# gimbaldriver.net
KiCad netlist of a schematic drawn in EAGLE
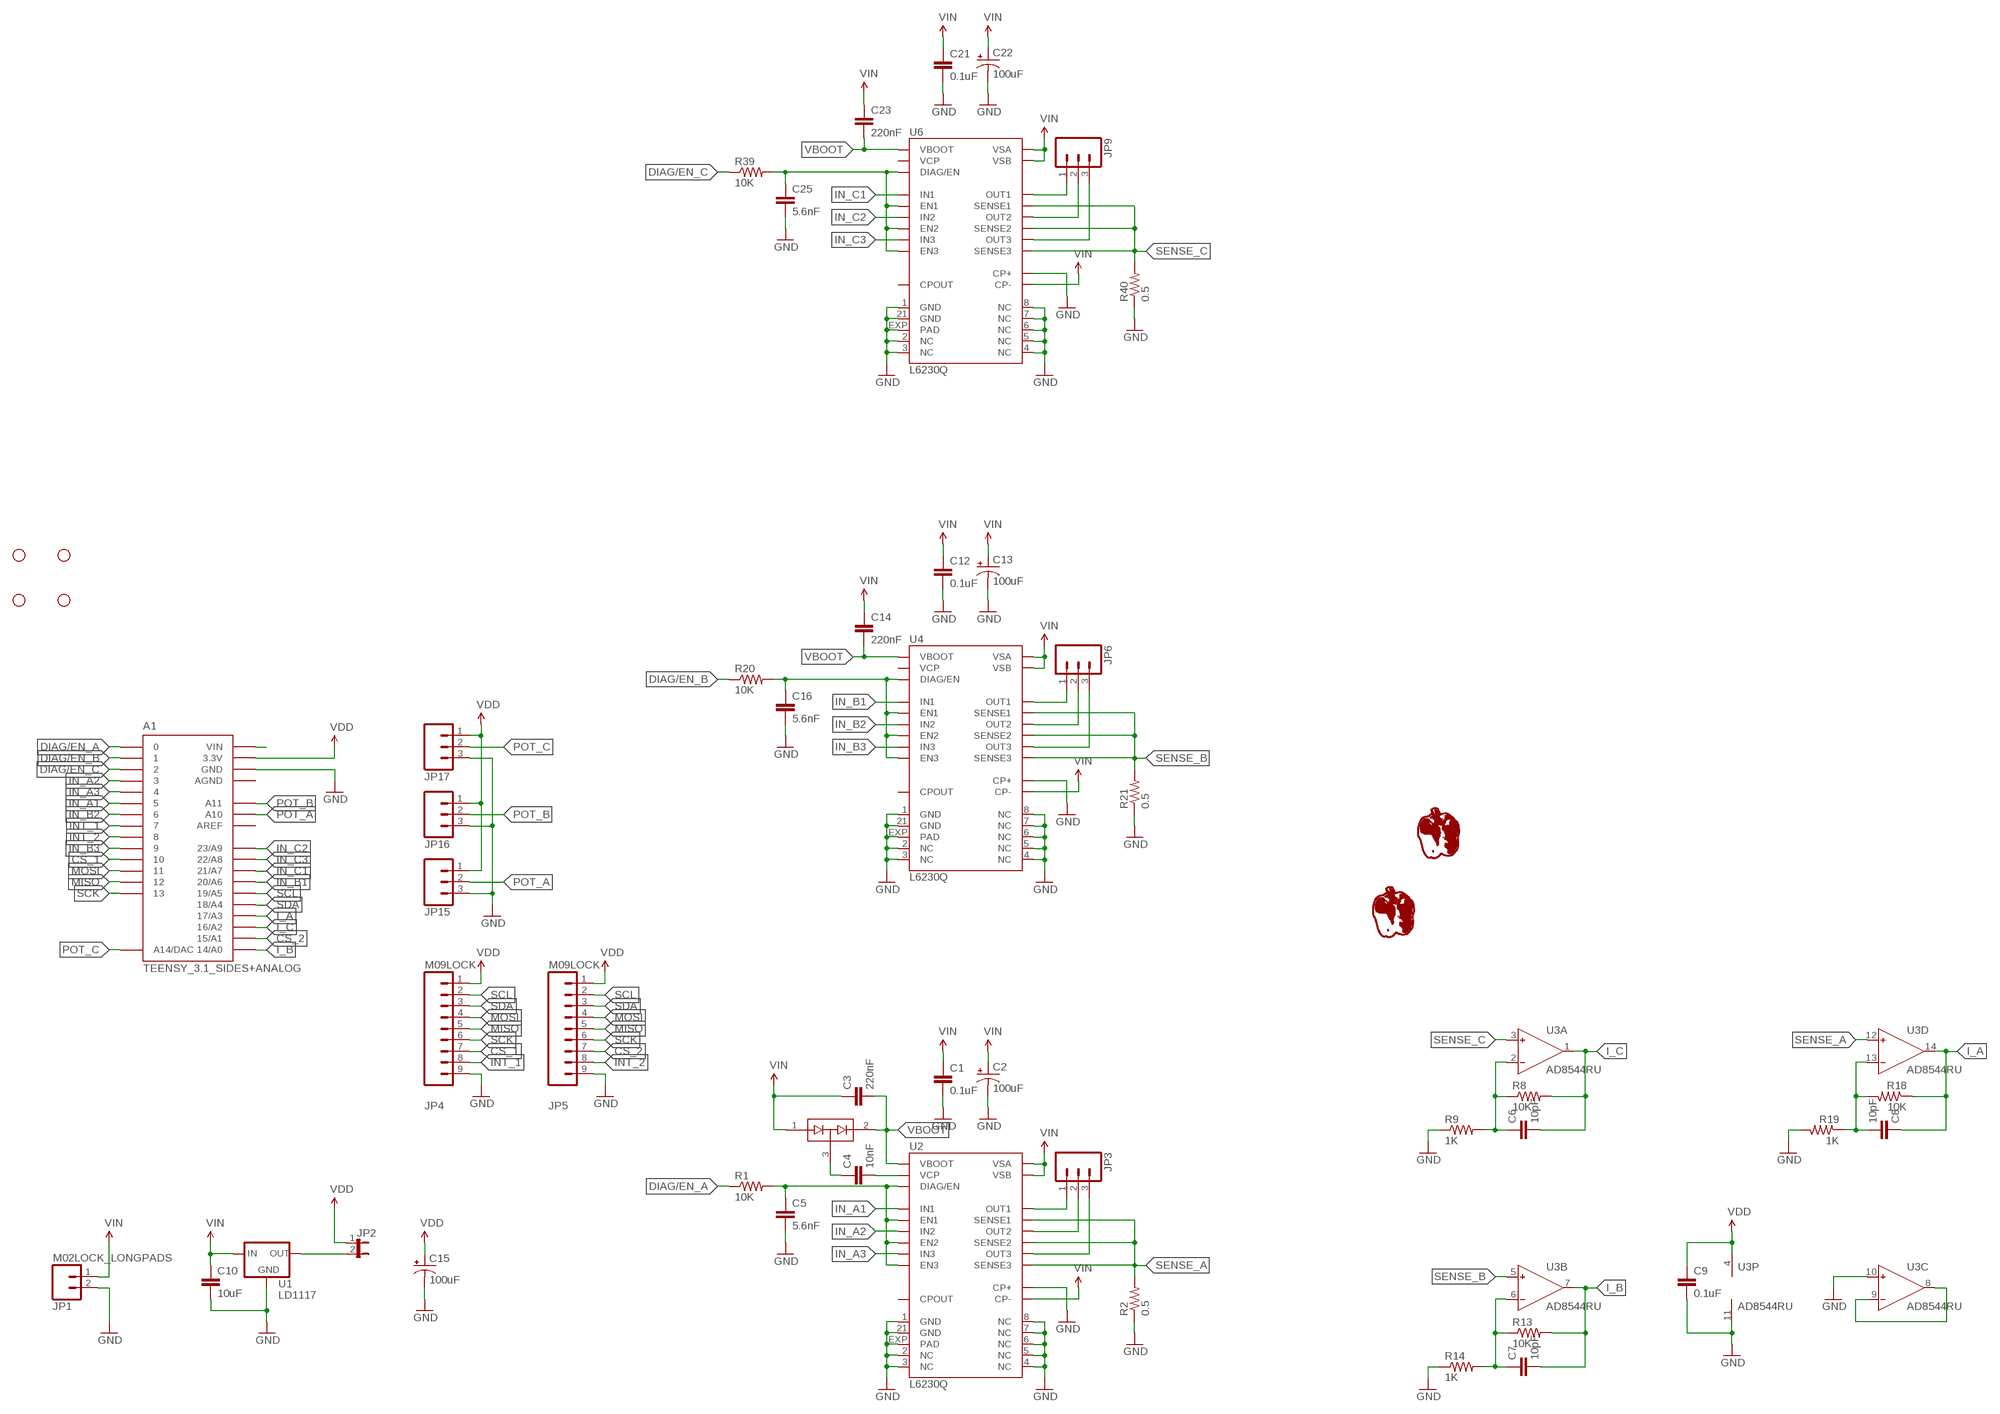
[diagram p0: schematic, sheet 1]

(export (version "E")
  (design (tool "Eeschema 10.0.6"))
  (components
    (comp (ref "A1")
      (value "TEENSY_3.1_SIDES+ANALOG")
      (footprint "eagle-import:TEENSY_3.1_SIDES+ANALOG")
      (libsource (lib "eagle-import") (part "TEENSY_3.1_SIDES+ANALOG"))
    )
    (comp (ref "C1")
      (value "0.1uF")
      (footprint "eagle-import:0603-CAP")
      (libsource (lib "eagle-import") (part "CAP0603-CAP"))
    )
    (comp (ref "C2")
      (value "100uF")
      (footprint "eagle-import:CPOL-RADIAL-100UF-25V")
      (libsource (lib "eagle-import") (part "CAP_POLPTH1"))
    )
    (comp (ref "C3")
      (value "220nF")
      (footprint "eagle-import:0603-CAP")
      (libsource (lib "eagle-import") (part "CAP0603-CAP"))
    )
    (comp (ref "C4")
      (value "10nF")
      (footprint "eagle-import:0603-CAP")
      (libsource (lib "eagle-import") (part "CAP0603-CAP"))
    )
    (comp (ref "C5")
      (value "5.6nF")
      (footprint "eagle-import:0603-CAP")
      (libsource (lib "eagle-import") (part "CAP0603-CAP"))
    )
    (comp (ref "C6")
      (value "10pF")
      (footprint "eagle-import:0603-CAP")
      (libsource (lib "eagle-import") (part "CAP0603-CAP"))
    )
    (comp (ref "C7")
      (value "10pF")
      (footprint "eagle-import:0603-CAP")
      (libsource (lib "eagle-import") (part "CAP0603-CAP"))
    )
    (comp (ref "C8")
      (value "10pF")
      (footprint "eagle-import:0603-CAP")
      (libsource (lib "eagle-import") (part "CAP0603-CAP"))
    )
    (comp (ref "C9")
      (value "0.1uF")
      (footprint "eagle-import:0603-CAP")
      (libsource (lib "eagle-import") (part "CAP0603-CAP"))
    )
    (comp (ref "C10")
      (value "10uF")
      (footprint "eagle-import:1206")
      (libsource (lib "eagle-import") (part "CAP1206"))
    )
    (comp (ref "C12")
      (value "0.1uF")
      (footprint "eagle-import:0603-CAP")
      (libsource (lib "eagle-import") (part "CAP0603-CAP"))
    )
    (comp (ref "C13")
      (value "100uF")
      (footprint "eagle-import:CPOL-RADIAL-100UF-25V")
      (libsource (lib "eagle-import") (part "CAP_POLPTH1"))
    )
    (comp (ref "C14")
      (value "220nF")
      (footprint "eagle-import:0603-CAP")
      (libsource (lib "eagle-import") (part "CAP0603-CAP"))
    )
    (comp (ref "C15")
      (value "100uF")
      (footprint "eagle-import:CPOL-RADIAL-100UF-25V")
      (libsource (lib "eagle-import") (part "CAP_POLPTH1"))
    )
    (comp (ref "C16")
      (value "5.6nF")
      (footprint "eagle-import:0603-CAP")
      (libsource (lib "eagle-import") (part "CAP0603-CAP"))
    )
    (comp (ref "C21")
      (value "0.1uF")
      (footprint "eagle-import:0603-CAP")
      (libsource (lib "eagle-import") (part "CAP0603-CAP"))
    )
    (comp (ref "C22")
      (value "100uF")
      (footprint "eagle-import:CPOL-RADIAL-100UF-25V")
      (libsource (lib "eagle-import") (part "CAP_POLPTH1"))
    )
    (comp (ref "C23")
      (value "220nF")
      (footprint "eagle-import:0603-CAP")
      (libsource (lib "eagle-import") (part "CAP0603-CAP"))
    )
    (comp (ref "C25")
      (value "5.6nF")
      (footprint "eagle-import:0603-CAP")
      (libsource (lib "eagle-import") (part "CAP0603-CAP"))
    )
    (comp (ref "D1")
      (value "BAV99")
      (footprint "eagle-import:SOT23")
      (libsource (lib "eagle-import") (part "BAV99"))
    )
    (comp (ref "JP1")
      (value "M02LOCK_LONGPADS")
      (footprint "eagle-import:1X02_LOCK_LONGPADS")
      (libsource (lib "eagle-import") (part "M02LOCK_LONGPADS"))
    )
    (comp (ref "JP2")
      (value "JUMPER-2PTH_LOCK")
      (footprint "eagle-import:1X02_LOCK")
      (libsource (lib "eagle-import") (part "JUMPER-2PTH_LOCK"))
    )
    (comp (ref "JP3")
      (value "M03LOCK_LONGPADS")
      (footprint "eagle-import:1X03_LOCK_LONGPADS")
      (libsource (lib "eagle-import") (part "M03LOCK_LONGPADS"))
    )
    (comp (ref "JP4")
      (value "M09LOCK")
      (footprint "eagle-import:1X09_LOCK")
      (libsource (lib "eagle-import") (part "M09LOCK"))
    )
    (comp (ref "JP5")
      (value "M09LOCK")
      (footprint "eagle-import:1X09_LOCK")
      (libsource (lib "eagle-import") (part "M09LOCK"))
    )
    (comp (ref "JP6")
      (value "M03LOCK_LONGPADS")
      (footprint "eagle-import:1X03_LOCK_LONGPADS")
      (libsource (lib "eagle-import") (part "M03LOCK_LONGPADS"))
    )
    (comp (ref "JP9")
      (value "M03LOCK_LONGPADS")
      (footprint "eagle-import:1X03_LOCK_LONGPADS")
      (libsource (lib "eagle-import") (part "M03LOCK_LONGPADS"))
    )
    (comp (ref "JP15")
      (value "M03LOCK")
      (footprint "eagle-import:1X03_LOCK")
      (libsource (lib "eagle-import") (part "M03LOCK"))
    )
    (comp (ref "JP16")
      (value "M03LOCK")
      (footprint "eagle-import:1X03_LOCK")
      (libsource (lib "eagle-import") (part "M03LOCK"))
    )
    (comp (ref "JP17")
      (value "M03LOCK")
      (footprint "eagle-import:1X03_LOCK")
      (libsource (lib "eagle-import") (part "M03LOCK"))
    )
    (comp (ref "R1")
      (value "10K")
      (footprint "eagle-import:0603-RES")
      (libsource (lib "eagle-import") (part "RESISTOR0603-RES"))
    )
    (comp (ref "R2")
      (value "0.5")
      (footprint "eagle-import:1206")
      (libsource (lib "eagle-import") (part "RESISTOR1206"))
    )
    (comp (ref "R8")
      (value "10K")
      (footprint "eagle-import:0603-RES")
      (libsource (lib "eagle-import") (part "RESISTOR0603-RES"))
    )
    (comp (ref "R9")
      (value "1K")
      (footprint "eagle-import:0603-RES")
      (libsource (lib "eagle-import") (part "RESISTOR0603-RES"))
    )
    (comp (ref "R13")
      (value "10K")
      (footprint "eagle-import:0603-RES")
      (libsource (lib "eagle-import") (part "RESISTOR0603-RES"))
    )
    (comp (ref "R14")
      (value "1K")
      (footprint "eagle-import:0603-RES")
      (libsource (lib "eagle-import") (part "RESISTOR0603-RES"))
    )
    (comp (ref "R18")
      (value "10K")
      (footprint "eagle-import:0603-RES")
      (libsource (lib "eagle-import") (part "RESISTOR0603-RES"))
    )
    (comp (ref "R19")
      (value "1K")
      (footprint "eagle-import:0603-RES")
      (libsource (lib "eagle-import") (part "RESISTOR0603-RES"))
    )
    (comp (ref "R20")
      (value "10K")
      (footprint "eagle-import:0603-RES")
      (libsource (lib "eagle-import") (part "RESISTOR0603-RES"))
    )
    (comp (ref "R21")
      (value "0.5")
      (footprint "eagle-import:1206")
      (libsource (lib "eagle-import") (part "RESISTOR1206"))
    )
    (comp (ref "R39")
      (value "10K")
      (footprint "eagle-import:0603-RES")
      (libsource (lib "eagle-import") (part "RESISTOR0603-RES"))
    )
    (comp (ref "R40")
      (value "0.5")
      (footprint "eagle-import:1206")
      (libsource (lib "eagle-import") (part "RESISTOR1206"))
    )
    (comp (ref "STANDOFF1")
      (value "STAND-OFF")
      (footprint "eagle-import:STAND-OFF")
      (libsource (lib "eagle-import") (part "STAND-OFF"))
    )
    (comp (ref "STANDOFF2")
      (value "STAND-OFF")
      (footprint "eagle-import:STAND-OFF")
      (libsource (lib "eagle-import") (part "STAND-OFF"))
    )
    (comp (ref "STANDOFF3")
      (value "STAND-OFF")
      (footprint "eagle-import:STAND-OFF")
      (libsource (lib "eagle-import") (part "STAND-OFF"))
    )
    (comp (ref "STANDOFF4")
      (value "STAND-OFF")
      (footprint "eagle-import:STAND-OFF")
      (libsource (lib "eagle-import") (part "STAND-OFF"))
    )
    (comp (ref "U$1")
      (value "GIMP-PEPPER")
      (footprint "eagle-import:GIMP-PEPPER")
      (libsource (lib "eagle-import") (part "GIMP-PEPPER"))
    )
    (comp (ref "U$2")
      (value "GIMBALV1")
      (footprint "eagle-import:GIMBALV1")
      (libsource (lib "eagle-import") (part "GIMBALV1"))
    )
    (comp (ref "U1")
      (value "LD1117")
      (footprint "eagle-import:SOT-223")
      (libsource (lib "eagle-import") (part "LD1117"))
    )
    (comp (ref "U2")
      (value "L6230Q")
      (footprint "eagle-import:VFQFPN-32")
      (libsource (lib "eagle-import") (part "L6230Q"))
    )
    (comp (ref "U3")
      (value "AD8544RU")
      (footprint "eagle-import:TSSOP14")
      (fields (field (name "MPN") "AD8544ARUZ"))
      (libsource (lib "eagle-import") (part "AD8544RU"))
    )
    (comp (ref "U4")
      (value "L6230Q")
      (footprint "eagle-import:VFQFPN-32")
      (libsource (lib "eagle-import") (part "L6230Q"))
    )
    (comp (ref "U6")
      (value "L6230Q")
      (footprint "eagle-import:VFQFPN-32")
      (libsource (lib "eagle-import") (part "L6230Q"))
    )
  )
  (nets
    (net (code "1") (name "/AGND") (class "Default")
      (node (ref "A1") (pin "AGND") (pinfunction "AGND_AGND") (pintype "power_in"))
    )
    (net (code "2") (name "CS_1") (class "Default")
      (node (ref "A1") (pin "10") (pinfunction "10_10") (pintype "bidirectional"))
      (node (ref "JP4") (pin "7") (pinfunction "7_7") (pintype "passive"))
    )
    (net (code "3") (name "CS_2") (class "Default")
      (node (ref "A1") (pin "15/A1") (pinfunction "15/A1_15/A1") (pintype "bidirectional"))
      (node (ref "JP5") (pin "7") (pinfunction "7_7") (pintype "passive"))
    )
    (net (code "4") (name "DIAG{slash}EN_A") (class "Default")
      (node (ref "A1") (pin "0") (pinfunction "0_0") (pintype "bidirectional"))
      (node (ref "R1") (pin "1") (pinfunction "1_1") (pintype "passive"))
    )
    (net (code "5") (name "DIAG{slash}EN_B") (class "Default")
      (node (ref "A1") (pin "1") (pinfunction "1_1") (pintype "bidirectional"))
      (node (ref "R20") (pin "1") (pinfunction "1_1") (pintype "passive"))
    )
    (net (code "6") (name "DIAG{slash}EN_C") (class "Default")
      (node (ref "A1") (pin "2") (pinfunction "2_2") (pintype "bidirectional"))
      (node (ref "R39") (pin "1") (pinfunction "1_1") (pintype "passive"))
    )
    (net (code "7") (name "GND") (class "Default")
      (node (ref "A1") (pin "GND") (pinfunction "GND_GND") (pintype "power_in"))
      (node (ref "C1") (pin "2") (pinfunction "2_2") (pintype "passive"))
      (node (ref "C10") (pin "2") (pinfunction "2_2") (pintype "passive"))
      (node (ref "C12") (pin "2") (pinfunction "2_2") (pintype "passive"))
      (node (ref "C13") (pin "2") (pinfunction "-_2") (pintype "passive"))
      (node (ref "C15") (pin "2") (pinfunction "-_2") (pintype "passive"))
      (node (ref "C16") (pin "2") (pinfunction "2_2") (pintype "passive"))
      (node (ref "C2") (pin "2") (pinfunction "-_2") (pintype "passive"))
      (node (ref "C21") (pin "2") (pinfunction "2_2") (pintype "passive"))
      (node (ref "C22") (pin "2") (pinfunction "-_2") (pintype "passive"))
      (node (ref "C25") (pin "2") (pinfunction "2_2") (pintype "passive"))
      (node (ref "C5") (pin "2") (pinfunction "2_2") (pintype "passive"))
      (node (ref "C9") (pin "2") (pinfunction "2_2") (pintype "passive"))
      (node (ref "JP1") (pin "2") (pinfunction "2_2") (pintype "passive"))
      (node (ref "JP15") (pin "3") (pinfunction "3_3") (pintype "passive"))
      (node (ref "JP16") (pin "3") (pinfunction "3_3") (pintype "passive"))
      (node (ref "JP17") (pin "3") (pinfunction "3_3") (pintype "passive"))
      (node (ref "JP4") (pin "9") (pinfunction "9_9") (pintype "passive"))
      (node (ref "JP5") (pin "9") (pinfunction "9_9") (pintype "passive"))
      (node (ref "R14") (pin "1") (pinfunction "1_1") (pintype "passive"))
      (node (ref "R19") (pin "2") (pinfunction "2_2") (pintype "passive"))
      (node (ref "R2") (pin "1") (pinfunction "1_1") (pintype "passive"))
      (node (ref "R21") (pin "1") (pinfunction "1_1") (pintype "passive"))
      (node (ref "R40") (pin "1") (pinfunction "1_1") (pintype "passive"))
      (node (ref "R9") (pin "1") (pinfunction "1_1") (pintype "passive"))
      (node (ref "U1") (pin "1") (pinfunction "GND_1") (pintype "input"))
      (node (ref "U2") (pin "1") (pinfunction "GND_1") (pintype "bidirectional"))
      (node (ref "U2") (pin "2") (pinfunction "NC_2") (pintype "bidirectional"))
      (node (ref "U2") (pin "21") (pinfunction "GND_21") (pintype "bidirectional"))
      (node (ref "U2") (pin "3") (pinfunction "NC_3") (pintype "bidirectional"))
      (node (ref "U2") (pin "30") (pinfunction "CP+_30") (pintype "bidirectional"))
      (node (ref "U2") (pin "4") (pinfunction "NC_4") (pintype "bidirectional"))
      (node (ref "U2") (pin "5") (pinfunction "NC_5") (pintype "bidirectional"))
      (node (ref "U2") (pin "6") (pinfunction "NC_6") (pintype "bidirectional"))
      (node (ref "U2") (pin "7") (pinfunction "NC_7") (pintype "bidirectional"))
      (node (ref "U2") (pin "8") (pinfunction "NC_8") (pintype "bidirectional"))
      (node (ref "U2") (pin "EXP") (pinfunction "PAD_EXP") (pintype "bidirectional"))
      (node (ref "U3") (pin "10") (pinfunction "IN+_10") (pintype "input"))
      (node (ref "U3") (pin "11") (pinfunction "V-_11") (pintype "power_in"))
      (node (ref "U4") (pin "1") (pinfunction "GND_1") (pintype "bidirectional"))
      (node (ref "U4") (pin "2") (pinfunction "NC_2") (pintype "bidirectional"))
      (node (ref "U4") (pin "21") (pinfunction "GND_21") (pintype "bidirectional"))
      (node (ref "U4") (pin "3") (pinfunction "NC_3") (pintype "bidirectional"))
      (node (ref "U4") (pin "30") (pinfunction "CP+_30") (pintype "bidirectional"))
      (node (ref "U4") (pin "4") (pinfunction "NC_4") (pintype "bidirectional"))
      (node (ref "U4") (pin "5") (pinfunction "NC_5") (pintype "bidirectional"))
      (node (ref "U4") (pin "6") (pinfunction "NC_6") (pintype "bidirectional"))
      (node (ref "U4") (pin "7") (pinfunction "NC_7") (pintype "bidirectional"))
      (node (ref "U4") (pin "8") (pinfunction "NC_8") (pintype "bidirectional"))
      (node (ref "U4") (pin "EXP") (pinfunction "PAD_EXP") (pintype "bidirectional"))
      (node (ref "U6") (pin "1") (pinfunction "GND_1") (pintype "bidirectional"))
      (node (ref "U6") (pin "2") (pinfunction "NC_2") (pintype "bidirectional"))
      (node (ref "U6") (pin "21") (pinfunction "GND_21") (pintype "bidirectional"))
      (node (ref "U6") (pin "3") (pinfunction "NC_3") (pintype "bidirectional"))
      (node (ref "U6") (pin "30") (pinfunction "CP+_30") (pintype "bidirectional"))
      (node (ref "U6") (pin "4") (pinfunction "NC_4") (pintype "bidirectional"))
      (node (ref "U6") (pin "5") (pinfunction "NC_5") (pintype "bidirectional"))
      (node (ref "U6") (pin "6") (pinfunction "NC_6") (pintype "bidirectional"))
      (node (ref "U6") (pin "7") (pinfunction "NC_7") (pintype "bidirectional"))
      (node (ref "U6") (pin "8") (pinfunction "NC_8") (pintype "bidirectional"))
      (node (ref "U6") (pin "EXP") (pinfunction "PAD_EXP") (pintype "bidirectional"))
    )
    (net (code "8") (name "INT_1") (class "Default")
      (node (ref "A1") (pin "7") (pinfunction "7_7") (pintype "bidirectional"))
      (node (ref "JP4") (pin "8") (pinfunction "8_8") (pintype "passive"))
    )
    (net (code "9") (name "INT_2") (class "Default")
      (node (ref "A1") (pin "8") (pinfunction "8_8") (pintype "bidirectional"))
      (node (ref "JP5") (pin "8") (pinfunction "8_8") (pintype "passive"))
    )
    (net (code "10") (name "IN_A1") (class "Default")
      (node (ref "A1") (pin "5") (pinfunction "5_5") (pintype "bidirectional"))
      (node (ref "U2") (pin "26") (pinfunction "IN1_26") (pintype "bidirectional"))
    )
    (net (code "11") (name "IN_A2") (class "Default")
      (node (ref "A1") (pin "3") (pinfunction "3_3") (pintype "bidirectional"))
      (node (ref "U2") (pin "13") (pinfunction "IN2_13") (pintype "bidirectional"))
    )
    (net (code "12") (name "IN_A3") (class "Default")
      (node (ref "A1") (pin "4") (pinfunction "4_4") (pintype "bidirectional"))
      (node (ref "U2") (pin "28") (pinfunction "IN3_28") (pintype "bidirectional"))
    )
    (net (code "13") (name "IN_B1") (class "Default")
      (node (ref "A1") (pin "20/A6") (pinfunction "20/A6_20/A6") (pintype "bidirectional"))
      (node (ref "U4") (pin "26") (pinfunction "IN1_26") (pintype "bidirectional"))
    )
    (net (code "14") (name "IN_B2") (class "Default")
      (node (ref "A1") (pin "6") (pinfunction "6_6") (pintype "bidirectional"))
      (node (ref "U4") (pin "13") (pinfunction "IN2_13") (pintype "bidirectional"))
    )
    (net (code "15") (name "IN_B3") (class "Default")
      (node (ref "A1") (pin "9") (pinfunction "9_9") (pintype "bidirectional"))
      (node (ref "U4") (pin "28") (pinfunction "IN3_28") (pintype "bidirectional"))
    )
    (net (code "16") (name "IN_C1") (class "Default")
      (node (ref "A1") (pin "21/A7") (pinfunction "21/A7_21/A7") (pintype "bidirectional"))
      (node (ref "U6") (pin "26") (pinfunction "IN1_26") (pintype "bidirectional"))
    )
    (net (code "17") (name "IN_C2") (class "Default")
      (node (ref "A1") (pin "23/A9") (pinfunction "23/A9_23/A9") (pintype "bidirectional"))
      (node (ref "U6") (pin "13") (pinfunction "IN2_13") (pintype "bidirectional"))
    )
    (net (code "18") (name "IN_C3") (class "Default")
      (node (ref "A1") (pin "22/A8") (pinfunction "22/A8_22/A8") (pintype "bidirectional"))
      (node (ref "U6") (pin "28") (pinfunction "IN3_28") (pintype "bidirectional"))
    )
    (net (code "19") (name "I_A") (class "Default")
      (node (ref "A1") (pin "17/A3") (pinfunction "17/A3_17/A3") (pintype "bidirectional"))
      (node (ref "C8") (pin "1") (pinfunction "1_1") (pintype "passive"))
      (node (ref "R18") (pin "1") (pinfunction "1_1") (pintype "passive"))
      (node (ref "U3") (pin "14") (pinfunction "OUT_14") (pintype "output"))
    )
    (net (code "20") (name "I_B") (class "Default")
      (node (ref "A1") (pin "14/A0") (pinfunction "14/A0_14/A0") (pintype "bidirectional"))
      (node (ref "C7") (pin "2") (pinfunction "2_2") (pintype "passive"))
      (node (ref "R13") (pin "2") (pinfunction "2_2") (pintype "passive"))
      (node (ref "U3") (pin "7") (pinfunction "OUT_7") (pintype "output"))
    )
    (net (code "21") (name "I_C") (class "Default")
      (node (ref "A1") (pin "16/A2") (pinfunction "16/A2_16/A2") (pintype "bidirectional"))
      (node (ref "C6") (pin "2") (pinfunction "2_2") (pintype "passive"))
      (node (ref "R8") (pin "2") (pinfunction "2_2") (pintype "passive"))
      (node (ref "U3") (pin "1") (pinfunction "OUT_1") (pintype "output"))
    )
    (net (code "22") (name "MISO") (class "Default")
      (node (ref "A1") (pin "12") (pinfunction "12_12") (pintype "bidirectional"))
      (node (ref "JP4") (pin "5") (pinfunction "5_5") (pintype "passive"))
      (node (ref "JP5") (pin "5") (pinfunction "5_5") (pintype "passive"))
    )
    (net (code "23") (name "MOSI") (class "Default")
      (node (ref "A1") (pin "11") (pinfunction "11_11") (pintype "bidirectional"))
      (node (ref "JP4") (pin "4") (pinfunction "4_4") (pintype "passive"))
      (node (ref "JP5") (pin "4") (pinfunction "4_4") (pintype "passive"))
    )
    (net (code "24") (name "Net-(D1-COM)") (class "Default")
      (node (ref "C4") (pin "1") (pinfunction "1_1") (pintype "passive"))
      (node (ref "D1") (pin "3") (pinfunction "COM_3") (pintype "bidirectional"))
    )
    (net (code "25") (name "Net-(JP2-Pad2)") (class "Default")
      (node (ref "JP2") (pin "2") (pinfunction "2_2") (pintype "passive"))
      (node (ref "U1") (pin "2") (pinfunction "OUT_2") (pintype "passive"))
      (node (ref "U1") (pin "4") (pinfunction "OUT_4") (pintype "passive"))
    )
    (net (code "26") (name "Net-(U2-DIAG{slash}EN)") (class "Default")
      (node (ref "C5") (pin "1") (pinfunction "1_1") (pintype "passive"))
      (node (ref "R1") (pin "2") (pinfunction "2_2") (pintype "passive"))
      (node (ref "U2") (pin "14") (pinfunction "EN2_14") (pintype "bidirectional"))
      (node (ref "U2") (pin "16") (pinfunction "EN3_16") (pintype "bidirectional"))
      (node (ref "U2") (pin "27") (pinfunction "EN1_27") (pintype "bidirectional"))
      (node (ref "U2") (pin "9") (pinfunction "DIAG/EN_9") (pintype "bidirectional"))
    )
    (net (code "27") (name "Net-(U2-OUT1)") (class "Default")
      (node (ref "JP3") (pin "1") (pinfunction "1_1") (pintype "passive"))
      (node (ref "U2") (pin "31") (pinfunction "OUT1_31") (pintype "bidirectional"))
    )
    (net (code "28") (name "Net-(U2-OUT2)") (class "Default")
      (node (ref "JP3") (pin "2") (pinfunction "2_2") (pintype "passive"))
      (node (ref "U2") (pin "23") (pinfunction "OUT2_23") (pintype "bidirectional"))
    )
    (net (code "29") (name "Net-(U2-OUT3)") (class "Default")
      (node (ref "JP3") (pin "3") (pinfunction "3_3") (pintype "passive"))
      (node (ref "U2") (pin "19") (pinfunction "OUT3_19") (pintype "bidirectional"))
    )
    (net (code "30") (name "Net-(U2-VCP)") (class "Default")
      (node (ref "C4") (pin "2") (pinfunction "2_2") (pintype "passive"))
      (node (ref "U2") (pin "24") (pinfunction "VCP_24") (pintype "bidirectional"))
    )
    (net (code "31") (name "Net-(U3A-IN-)") (class "Default")
      (node (ref "C6") (pin "1") (pinfunction "1_1") (pintype "passive"))
      (node (ref "R8") (pin "1") (pinfunction "1_1") (pintype "passive"))
      (node (ref "R9") (pin "2") (pinfunction "2_2") (pintype "passive"))
      (node (ref "U3") (pin "2") (pinfunction "IN-_2") (pintype "input"))
    )
    (net (code "32") (name "Net-(U3B-IN-)") (class "Default")
      (node (ref "C7") (pin "1") (pinfunction "1_1") (pintype "passive"))
      (node (ref "R13") (pin "1") (pinfunction "1_1") (pintype "passive"))
      (node (ref "R14") (pin "2") (pinfunction "2_2") (pintype "passive"))
      (node (ref "U3") (pin "6") (pinfunction "IN-_6") (pintype "input"))
    )
    (net (code "33") (name "Net-(U3C-IN-)") (class "Default")
      (node (ref "U3") (pin "8") (pinfunction "OUT_8") (pintype "output"))
      (node (ref "U3") (pin "9") (pinfunction "IN-_9") (pintype "input"))
    )
    (net (code "34") (name "Net-(U3D-IN-)") (class "Default")
      (node (ref "C8") (pin "2") (pinfunction "2_2") (pintype "passive"))
      (node (ref "R18") (pin "2") (pinfunction "2_2") (pintype "passive"))
      (node (ref "R19") (pin "1") (pinfunction "1_1") (pintype "passive"))
      (node (ref "U3") (pin "13") (pinfunction "IN-_13") (pintype "input"))
    )
    (net (code "35") (name "Net-(U4-DIAG{slash}EN)") (class "Default")
      (node (ref "C16") (pin "1") (pinfunction "1_1") (pintype "passive"))
      (node (ref "R20") (pin "2") (pinfunction "2_2") (pintype "passive"))
      (node (ref "U4") (pin "14") (pinfunction "EN2_14") (pintype "bidirectional"))
      (node (ref "U4") (pin "16") (pinfunction "EN3_16") (pintype "bidirectional"))
      (node (ref "U4") (pin "27") (pinfunction "EN1_27") (pintype "bidirectional"))
      (node (ref "U4") (pin "9") (pinfunction "DIAG/EN_9") (pintype "bidirectional"))
    )
    (net (code "36") (name "Net-(U4-OUT1)") (class "Default")
      (node (ref "JP6") (pin "1") (pinfunction "1_1") (pintype "passive"))
      (node (ref "U4") (pin "31") (pinfunction "OUT1_31") (pintype "bidirectional"))
    )
    (net (code "37") (name "Net-(U4-OUT2)") (class "Default")
      (node (ref "JP6") (pin "2") (pinfunction "2_2") (pintype "passive"))
      (node (ref "U4") (pin "23") (pinfunction "OUT2_23") (pintype "bidirectional"))
    )
    (net (code "38") (name "Net-(U4-OUT3)") (class "Default")
      (node (ref "JP6") (pin "3") (pinfunction "3_3") (pintype "passive"))
      (node (ref "U4") (pin "19") (pinfunction "OUT3_19") (pintype "bidirectional"))
    )
    (net (code "39") (name "Net-(U6-DIAG{slash}EN)") (class "Default")
      (node (ref "C25") (pin "1") (pinfunction "1_1") (pintype "passive"))
      (node (ref "R39") (pin "2") (pinfunction "2_2") (pintype "passive"))
      (node (ref "U6") (pin "14") (pinfunction "EN2_14") (pintype "bidirectional"))
      (node (ref "U6") (pin "16") (pinfunction "EN3_16") (pintype "bidirectional"))
      (node (ref "U6") (pin "27") (pinfunction "EN1_27") (pintype "bidirectional"))
      (node (ref "U6") (pin "9") (pinfunction "DIAG/EN_9") (pintype "bidirectional"))
    )
    (net (code "40") (name "Net-(U6-OUT1)") (class "Default")
      (node (ref "JP9") (pin "1") (pinfunction "1_1") (pintype "passive"))
      (node (ref "U6") (pin "31") (pinfunction "OUT1_31") (pintype "bidirectional"))
    )
    (net (code "41") (name "Net-(U6-OUT2)") (class "Default")
      (node (ref "JP9") (pin "2") (pinfunction "2_2") (pintype "passive"))
      (node (ref "U6") (pin "23") (pinfunction "OUT2_23") (pintype "bidirectional"))
    )
    (net (code "42") (name "Net-(U6-OUT3)") (class "Default")
      (node (ref "JP9") (pin "3") (pinfunction "3_3") (pintype "passive"))
      (node (ref "U6") (pin "19") (pinfunction "OUT3_19") (pintype "bidirectional"))
    )
    (net (code "43") (name "POT_A") (class "Default")
      (node (ref "A1") (pin "A10") (pinfunction "A10_A10") (pintype "bidirectional"))
      (node (ref "JP15") (pin "2") (pinfunction "2_2") (pintype "passive"))
    )
    (net (code "44") (name "POT_B") (class "Default")
      (node (ref "A1") (pin "A11") (pinfunction "A11_A11") (pintype "bidirectional"))
      (node (ref "JP16") (pin "2") (pinfunction "2_2") (pintype "passive"))
    )
    (net (code "45") (name "POT_C") (class "Default")
      (node (ref "A1") (pin "RST") (pinfunction "A14/DAC_RST") (pintype "bidirectional"))
      (node (ref "JP17") (pin "2") (pinfunction "2_2") (pintype "passive"))
    )
    (net (code "46") (name "SCK") (class "Default")
      (node (ref "A1") (pin "13") (pinfunction "13_13") (pintype "bidirectional"))
      (node (ref "JP4") (pin "6") (pinfunction "6_6") (pintype "passive"))
      (node (ref "JP5") (pin "6") (pinfunction "6_6") (pintype "passive"))
    )
    (net (code "47") (name "SCL") (class "Default")
      (node (ref "A1") (pin "19/A5") (pinfunction "19/A5_19/A5") (pintype "bidirectional"))
      (node (ref "JP4") (pin "2") (pinfunction "2_2") (pintype "passive"))
      (node (ref "JP5") (pin "2") (pinfunction "2_2") (pintype "passive"))
    )
    (net (code "48") (name "SDA") (class "Default")
      (node (ref "A1") (pin "18/A4") (pinfunction "18/A4_18/A4") (pintype "bidirectional"))
      (node (ref "JP4") (pin "3") (pinfunction "3_3") (pintype "passive"))
      (node (ref "JP5") (pin "3") (pinfunction "3_3") (pintype "passive"))
    )
    (net (code "49") (name "SENSE_A") (class "Default")
      (node (ref "R2") (pin "2") (pinfunction "2_2") (pintype "passive"))
      (node (ref "U2") (pin "12") (pinfunction "SENSE3_12") (pintype "bidirectional"))
      (node (ref "U2") (pin "25") (pinfunction "SENSE2_25") (pintype "bidirectional"))
      (node (ref "U2") (pin "29") (pinfunction "SENSE1_29") (pintype "bidirectional"))
      (node (ref "U3") (pin "12") (pinfunction "IN+_12") (pintype "input"))
    )
    (net (code "50") (name "SENSE_B") (class "Default")
      (node (ref "R21") (pin "2") (pinfunction "2_2") (pintype "passive"))
      (node (ref "U3") (pin "5") (pinfunction "IN+_5") (pintype "input"))
      (node (ref "U4") (pin "12") (pinfunction "SENSE3_12") (pintype "bidirectional"))
      (node (ref "U4") (pin "25") (pinfunction "SENSE2_25") (pintype "bidirectional"))
      (node (ref "U4") (pin "29") (pinfunction "SENSE1_29") (pintype "bidirectional"))
    )
    (net (code "51") (name "SENSE_C") (class "Default")
      (node (ref "R40") (pin "2") (pinfunction "2_2") (pintype "passive"))
      (node (ref "U3") (pin "3") (pinfunction "IN+_3") (pintype "input"))
      (node (ref "U6") (pin "12") (pinfunction "SENSE3_12") (pintype "bidirectional"))
      (node (ref "U6") (pin "25") (pinfunction "SENSE2_25") (pintype "bidirectional"))
      (node (ref "U6") (pin "29") (pinfunction "SENSE1_29") (pintype "bidirectional"))
    )
    (net (code "52") (name "VBOOT") (class "Default")
      (node (ref "C14") (pin "2") (pinfunction "2_2") (pintype "passive"))
      (node (ref "C23") (pin "2") (pinfunction "2_2") (pintype "passive"))
      (node (ref "C3") (pin "2") (pinfunction "2_2") (pintype "passive"))
      (node (ref "D1") (pin "2") (pinfunction "C2_2") (pintype "bidirectional"))
      (node (ref "U2") (pin "17") (pinfunction "VBOOT_17") (pintype "bidirectional"))
      (node (ref "U4") (pin "17") (pinfunction "VBOOT_17") (pintype "bidirectional"))
      (node (ref "U6") (pin "17") (pinfunction "VBOOT_17") (pintype "bidirectional"))
    )
    (net (code "53") (name "VDD") (class "Default")
      (node (ref "A1") (pin "3.3V") (pinfunction "3.3V_3.3V") (pintype "power_in"))
      (node (ref "C15") (pin "1") (pinfunction "+_1") (pintype "passive"))
      (node (ref "C9") (pin "1") (pinfunction "1_1") (pintype "passive"))
      (node (ref "JP15") (pin "1") (pinfunction "1_1") (pintype "passive"))
      (node (ref "JP16") (pin "1") (pinfunction "1_1") (pintype "passive"))
      (node (ref "JP17") (pin "1") (pinfunction "1_1") (pintype "passive"))
      (node (ref "JP2") (pin "1") (pinfunction "1_1") (pintype "passive"))
      (node (ref "JP4") (pin "1") (pinfunction "1_1") (pintype "passive"))
      (node (ref "JP5") (pin "1") (pinfunction "1_1") (pintype "passive"))
      (node (ref "U3") (pin "4") (pinfunction "V+_4") (pintype "power_in"))
    )
    (net (code "54") (name "VIN") (class "Default")
      (node (ref "C1") (pin "1") (pinfunction "1_1") (pintype "passive"))
      (node (ref "C10") (pin "1") (pinfunction "1_1") (pintype "passive"))
      (node (ref "C12") (pin "1") (pinfunction "1_1") (pintype "passive"))
      (node (ref "C13") (pin "1") (pinfunction "+_1") (pintype "passive"))
      (node (ref "C14") (pin "1") (pinfunction "1_1") (pintype "passive"))
      (node (ref "C2") (pin "1") (pinfunction "+_1") (pintype "passive"))
      (node (ref "C21") (pin "1") (pinfunction "1_1") (pintype "passive"))
      (node (ref "C22") (pin "1") (pinfunction "+_1") (pintype "passive"))
      (node (ref "C23") (pin "1") (pinfunction "1_1") (pintype "passive"))
      (node (ref "C3") (pin "1") (pinfunction "1_1") (pintype "passive"))
      (node (ref "D1") (pin "1") (pinfunction "A1_1") (pintype "bidirectional"))
      (node (ref "JP1") (pin "1") (pinfunction "1_1") (pintype "passive"))
      (node (ref "U1") (pin "3") (pinfunction "IN_3") (pintype "input"))
      (node (ref "U2") (pin "15") (pinfunction "CP-_15") (pintype "bidirectional"))
      (node (ref "U2") (pin "20") (pinfunction "VSB_20") (pintype "bidirectional"))
      (node (ref "U2") (pin "22") (pinfunction "VSA_22") (pintype "bidirectional"))
      (node (ref "U4") (pin "15") (pinfunction "CP-_15") (pintype "bidirectional"))
      (node (ref "U4") (pin "20") (pinfunction "VSB_20") (pintype "bidirectional"))
      (node (ref "U4") (pin "22") (pinfunction "VSA_22") (pintype "bidirectional"))
      (node (ref "U6") (pin "15") (pinfunction "CP-_15") (pintype "bidirectional"))
      (node (ref "U6") (pin "20") (pinfunction "VSB_20") (pintype "bidirectional"))
      (node (ref "U6") (pin "22") (pinfunction "VSA_22") (pintype "bidirectional"))
    )
    (net (code "55") (name "unconnected-(A1-PadAREF)") (class "Default")
      (node (ref "A1") (pin "AREF") (pinfunction "AREF_AREF") (pintype "bidirectional"))
    )
    (net (code "56") (name "unconnected-(A1-PadVIN)") (class "Default")
      (node (ref "A1") (pin "VIN") (pinfunction "VIN_VIN") (pintype "power_in"))
    )
    (net (code "57") (name "unconnected-(U2-CPOUT-Pad11)") (class "Default")
      (node (ref "U2") (pin "11") (pinfunction "CPOUT_11") (pintype "bidirectional"))
    )
    (net (code "58") (name "unconnected-(U4-CPOUT-Pad11)") (class "Default")
      (node (ref "U4") (pin "11") (pinfunction "CPOUT_11") (pintype "bidirectional"))
    )
    (net (code "59") (name "unconnected-(U4-VCP-Pad24)") (class "Default")
      (node (ref "U4") (pin "24") (pinfunction "VCP_24") (pintype "bidirectional"))
    )
    (net (code "60") (name "unconnected-(U6-CPOUT-Pad11)") (class "Default")
      (node (ref "U6") (pin "11") (pinfunction "CPOUT_11") (pintype "bidirectional"))
    )
    (net (code "61") (name "unconnected-(U6-VCP-Pad24)") (class "Default")
      (node (ref "U6") (pin "24") (pinfunction "VCP_24") (pintype "bidirectional"))
    )
  )
)
